# Power.net
KiCad netlist of a schematic drawn in Altium Designer
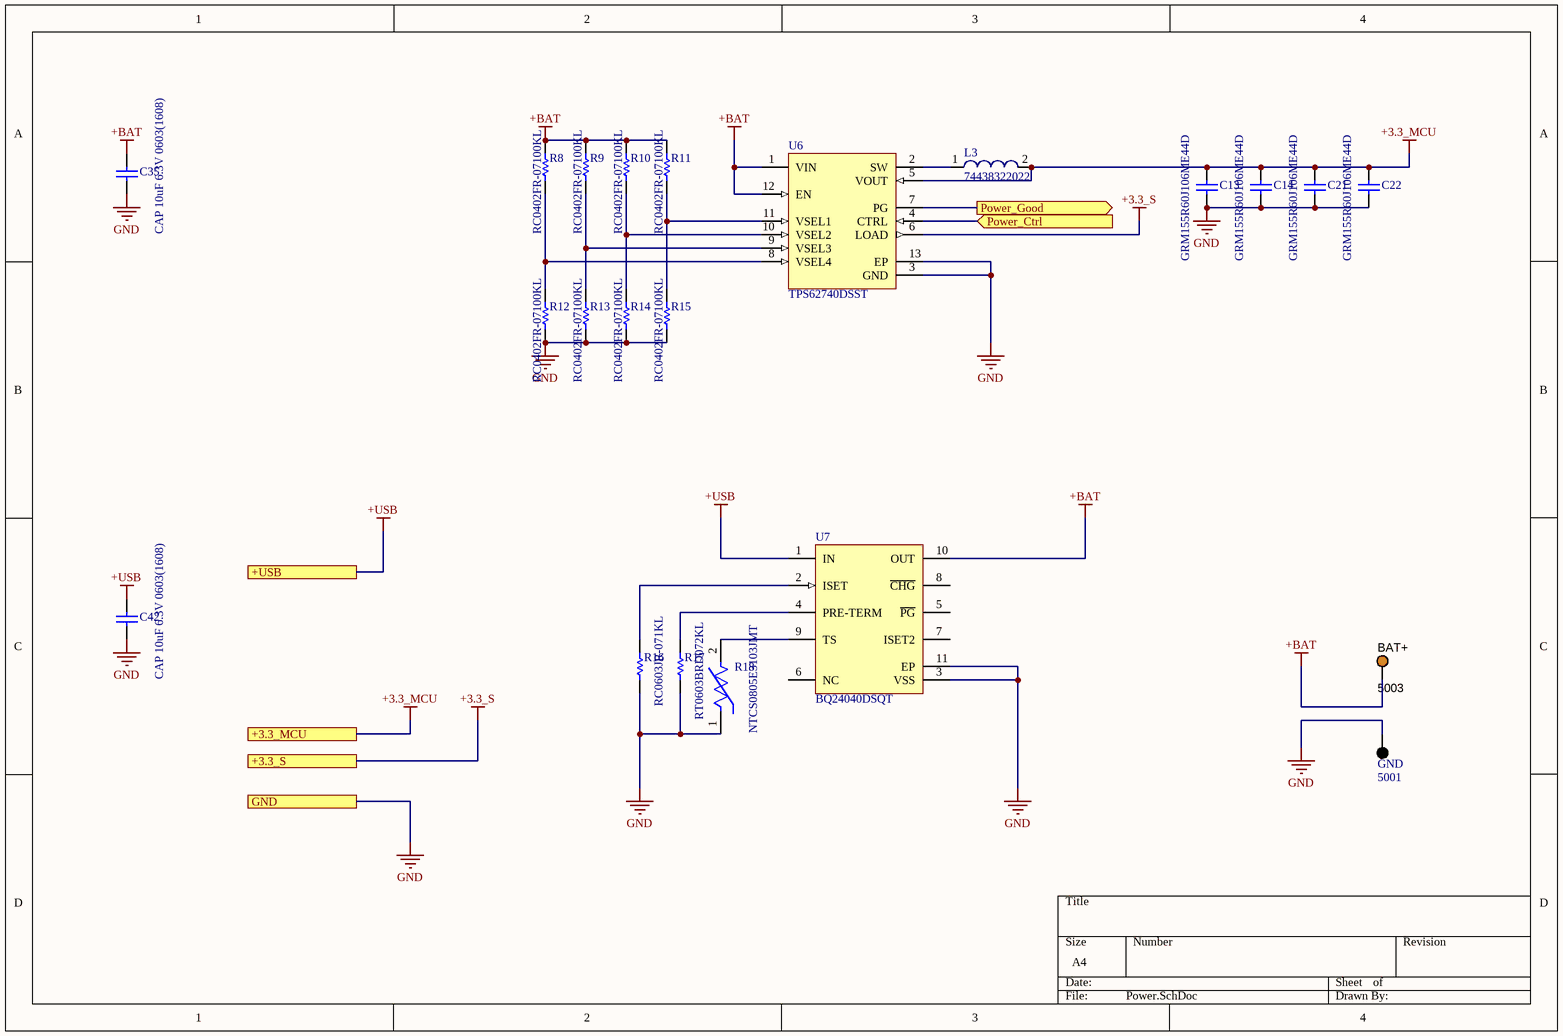
[diagram p0: Power.SchDoc]

(export (version "E")
  (design (tool "Eeschema 10.0.6"))
  (components
    (comp (ref "BAT+")
      (value "5003")
      (footprint "KSTN-5003")
      (description "Test Point, Orange, 1-Pin THD, RoHS")
      (libsource (lib "Altium Content Vault") (part "TESTPOINT_ORANGE"))
    )
    (comp (ref "C13")
      (value "GRM155R60J106ME44D")
      (footprint "MURA-GRM155R60J106ME44D-2_M")
      (fields (field (name "TOLERANCE") "20%") (field (name "MANUFACTURER") "Murata"))
      (libsource (lib "Altium Content Vault") (part "CAP-NP-2"))
    )
    (comp (ref "C14")
      (value "GRM155R60J106ME44D")
      (footprint "MURA-GRM155R60J106ME44D-2_M")
      (fields (field (name "TOLERANCE") "20%") (field (name "MANUFACTURER") "Murata"))
      (libsource (lib "Altium Content Vault") (part "CAP-NP-2"))
    )
    (comp (ref "C21")
      (value "GRM155R60J106ME44D")
      (footprint "MURA-GRM155R60J106ME44D-2_M")
      (fields (field (name "TOLERANCE") "20%") (field (name "MANUFACTURER") "Murata"))
      (libsource (lib "Altium Content Vault") (part "CAP-NP-2"))
    )
    (comp (ref "C22")
      (value "GRM155R60J106ME44D")
      (footprint "MURA-GRM155R60J106ME44D-2_M")
      (fields (field (name "TOLERANCE") "20%") (field (name "MANUFACTURER") "Murata"))
      (libsource (lib "Altium Content Vault") (part "CAP-NP-2"))
    )
    (comp (ref "C35")
      (value "CAP 10uF 6.3V 0603(1608)")
      (footprint "CAPC0603(1608)100_N")
      (description "CAP 10uF 6.3V ±20% 0603 (1608 Metric) Thickness 1mm SMD")
      (fields (field (name "TOLERANCE") "Â±20%"))
      (libsource (lib "Altium Content Vault") (part "CAP"))
    )
    (comp (ref "C42")
      (value "CAP 10uF 6.3V 0603(1608)")
      (footprint "CAPC0603(1608)100_N")
      (description "CAP 10uF 6.3V ±20% 0603 (1608 Metric) Thickness 1mm SMD")
      (fields (field (name "TOLERANCE") "Â±20%"))
      (libsource (lib "Altium Content Vault") (part "CAP"))
    )
    (comp (ref "GND")
      (value "5001")
      (footprint "KSTN-5001")
      (description "Test Point, Black, 1-Pin THD, RoHS, Bulk")
      (fields (field (name "MANUFACTURER") "Keystone"))
      (libsource (lib "Altium Content Vault") (part "KSTN-TP-5001"))
    )
    (comp (ref "L3")
      (value "74438322022")
      (footprint "SMD 2508")
      (description "Power Multilayer Inductor WE-MAPI, L=2.2µH")
      (fields (field (name "MANUFACTURER") "Wuerth Elektronik"))
      (libsource (lib "Altium Content Vault") (part "WE-IND-INDUCTOR-2"))
    )
    (comp (ref "R8")
      (value "RC0402FR-07100KL")
      (footprint "RESC1005X40X25NL05T10")
      (fields (field (name "MANUFACTURER") "Yageo / Phycomp"))
      (libsource (lib "Altium Content Vault") (part "RES"))
    )
    (comp (ref "R9")
      (value "RC0402FR-07100KL")
      (footprint "RESC1005X40X25NL05T10")
      (fields (field (name "MANUFACTURER") "Yageo / Phycomp"))
      (libsource (lib "Altium Content Vault") (part "RES"))
    )
    (comp (ref "R10")
      (value "RC0402FR-07100KL")
      (footprint "RESC1005X40X25NL05T10")
      (fields (field (name "MANUFACTURER") "Yageo / Phycomp"))
      (libsource (lib "Altium Content Vault") (part "RES"))
    )
    (comp (ref "R11")
      (value "RC0402FR-07100KL")
      (footprint "RESC1005X40X25NL05T10")
      (fields (field (name "MANUFACTURER") "Yageo / Phycomp"))
      (libsource (lib "Altium Content Vault") (part "RES"))
    )
    (comp (ref "R12")
      (value "RC0402FR-07100KL")
      (footprint "RESC1005X40X25NL05T10")
      (fields (field (name "MANUFACTURER") "Yageo / Phycomp"))
      (libsource (lib "Altium Content Vault") (part "RES"))
    )
    (comp (ref "R13")
      (value "RC0402FR-07100KL")
      (footprint "RESC1005X40X25NL05T10")
      (fields (field (name "MANUFACTURER") "Yageo / Phycomp"))
      (libsource (lib "Altium Content Vault") (part "RES"))
    )
    (comp (ref "R14")
      (value "RC0402FR-07100KL")
      (footprint "RESC1005X40X25NL05T10")
      (fields (field (name "MANUFACTURER") "Yageo / Phycomp"))
      (libsource (lib "Altium Content Vault") (part "RES"))
    )
    (comp (ref "R15")
      (value "RC0402FR-07100KL")
      (footprint "RESC1005X40X25NL05T10")
      (fields (field (name "MANUFACTURER") "Yageo / Phycomp"))
      (libsource (lib "Altium Content Vault") (part "RES"))
    )
    (comp (ref "R16")
      (value "RC0603JR-071KL")
      (footprint "RESC1608X55X25ML10T15")
      (description "Chip Resistor, 1 KOhm, +/- 5%, 0.063 W, -55 to 155 degC, 0603 (1608 Metric), RoHS, Tape and Reel")
      (fields (field (name "MANUFACTURER") "Yageo"))
      (libsource (lib "Altium Content Vault") (part "RES-2"))
    )
    (comp (ref "R17")
      (value "RT0603BRD072KL")
      (footprint "RESC1608X55X25ML10T15")
      (fields (field (name "MANUFACTURER") "Yageo"))
      (libsource (lib "Altium Content Vault") (part "RES"))
    )
    (comp (ref "R18")
      (value "NTCS0805E3103JMT")
      (footprint "FP-NTCS0805-MFG")
      (description "THERMISTOR NTC 10KOHM 3570K 0805")
      (fields
        (field (name "OCTOPART") "https://octopart.com/ntcs0805e3103jmt-vishay-39723061")
        (field (name "TOLERANCE") "5%")
      )
      (libsource (lib "Altium Content Vault") (part "3b148a6ebabc5fb4d708a66c052d352"))
    )
    (comp (ref "U6")
      (value "TPS62740DSST")
      (footprint "DSS0012A_V")
      (fields (field (name "PARTNUMBER") "TPS62740"))
      (libsource (lib "Altium Content Vault") (part "TI-TPS62740_2-WSON-12"))
    )
    (comp (ref "U7")
      (value "BQ24040DSQT")
      (footprint "DSQ0010A_V")
      (fields (field (name "MANUFACTURER") "Texas Instruments"))
      (libsource (lib "Altium Content Vault") (part "TI-BQ24040DSQ10-1500X900TP"))
    )
  )
  (nets
    (net (code "1") (name "+3.3_MCU") (class "Default")
      (node (ref "C13") (pin "2") (pinfunction "2_2") (pintype "passive"))
      (node (ref "C14") (pin "2") (pinfunction "2_2") (pintype "passive"))
      (node (ref "C21") (pin "2") (pinfunction "2_2") (pintype "passive"))
      (node (ref "C22") (pin "2") (pinfunction "2_2") (pintype "passive"))
      (node (ref "L3") (pin "2") (pinfunction "2_2") (pintype "passive"))
      (node (ref "U6") (pin "5") (pinfunction "VOUT_5") (pintype "input"))
    )
    (net (code "2") (name "+3.3_S") (class "Default")
      (node (ref "U6") (pin "6") (pinfunction "LOAD_6") (pintype "output"))
    )
    (net (code "3") (name "+BAT") (class "Default")
      (node (ref "BAT+") (pin "1") (pinfunction "1_1") (pintype "passive"))
      (node (ref "C35") (pin "2") (pinfunction "2_2") (pintype "passive"))
      (node (ref "R10") (pin "2") (pinfunction "2_2") (pintype "passive"))
      (node (ref "R11") (pin "2") (pinfunction "2_2") (pintype "passive"))
      (node (ref "R8") (pin "2") (pinfunction "2_2") (pintype "passive"))
      (node (ref "R9") (pin "2") (pinfunction "2_2") (pintype "passive"))
      (node (ref "U6") (pin "1") (pinfunction "VIN_1") (pintype "power_in"))
      (node (ref "U6") (pin "12") (pinfunction "EN_12") (pintype "input"))
      (node (ref "U7") (pin "10") (pinfunction "OUT_10") (pintype "power_in"))
    )
    (net (code "4") (name "+USB") (class "Default")
      (node (ref "C42") (pin "2") (pinfunction "2_2") (pintype "passive"))
      (node (ref "U7") (pin "1") (pinfunction "IN_1") (pintype "power_in"))
    )
    (net (code "5") (name "/Power_Ctrl") (class "Default")
      (node (ref "U6") (pin "4") (pinfunction "CTRL_4") (pintype "input"))
    )
    (net (code "6") (name "/Power_Good") (class "Default")
      (node (ref "U6") (pin "7") (pinfunction "PG_7") (pintype "tri_state"))
    )
    (net (code "7") (name "GND") (class "Default")
      (node (ref "C13") (pin "1") (pinfunction "1_1") (pintype "passive"))
      (node (ref "C14") (pin "1") (pinfunction "1_1") (pintype "passive"))
      (node (ref "C21") (pin "1") (pinfunction "1_1") (pintype "passive"))
      (node (ref "C22") (pin "1") (pinfunction "1_1") (pintype "passive"))
      (node (ref "C35") (pin "1") (pinfunction "1_1") (pintype "passive"))
      (node (ref "C42") (pin "1") (pinfunction "1_1") (pintype "passive"))
      (node (ref "GND") (pin "1") (pintype "passive"))
      (node (ref "R12") (pin "1") (pinfunction "1_1") (pintype "passive"))
      (node (ref "R13") (pin "1") (pinfunction "1_1") (pintype "passive"))
      (node (ref "R14") (pin "1") (pinfunction "1_1") (pintype "passive"))
      (node (ref "R15") (pin "1") (pinfunction "1_1") (pintype "passive"))
      (node (ref "R16") (pin "1") (pinfunction "1_1") (pintype "passive"))
      (node (ref "R17") (pin "1") (pinfunction "1_1") (pintype "passive"))
      (node (ref "R18") (pin "1") (pinfunction "1_1") (pintype "passive"))
      (node (ref "U6") (pin "13") (pinfunction "EP_13") (pintype "power_in"))
      (node (ref "U6") (pin "3") (pinfunction "GND_3") (pintype "power_in"))
      (node (ref "U7") (pin "11") (pinfunction "EP_11") (pintype "power_in"))
      (node (ref "U7") (pin "3") (pinfunction "VSS_3") (pintype "power_in"))
    )
    (net (code "8") (name "Net-(U6-SW)") (class "Default")
      (node (ref "L3") (pin "1") (pinfunction "1_1") (pintype "passive"))
      (node (ref "U6") (pin "2") (pinfunction "SW_2") (pintype "power_in"))
    )
    (net (code "9") (name "Net-(U6-VSEL1)") (class "Default")
      (node (ref "R11") (pin "1") (pinfunction "1_1") (pintype "passive"))
      (node (ref "R15") (pin "2") (pinfunction "2_2") (pintype "passive"))
      (node (ref "U6") (pin "11") (pinfunction "VSEL1_11") (pintype "input"))
    )
    (net (code "10") (name "Net-(U6-VSEL2)") (class "Default")
      (node (ref "R10") (pin "1") (pinfunction "1_1") (pintype "passive"))
      (node (ref "R14") (pin "2") (pinfunction "2_2") (pintype "passive"))
      (node (ref "U6") (pin "10") (pinfunction "VSEL2_10") (pintype "input"))
    )
    (net (code "11") (name "Net-(U6-VSEL3)") (class "Default")
      (node (ref "R13") (pin "2") (pinfunction "2_2") (pintype "passive"))
      (node (ref "R9") (pin "1") (pinfunction "1_1") (pintype "passive"))
      (node (ref "U6") (pin "9") (pinfunction "VSEL3_9") (pintype "input"))
    )
    (net (code "12") (name "Net-(U6-VSEL4)") (class "Default")
      (node (ref "R12") (pin "2") (pinfunction "2_2") (pintype "passive"))
      (node (ref "R8") (pin "1") (pinfunction "1_1") (pintype "passive"))
      (node (ref "U6") (pin "8") (pinfunction "VSEL4_8") (pintype "input"))
    )
    (net (code "13") (name "Net-(U7-ISET)") (class "Default")
      (node (ref "R16") (pin "2") (pinfunction "2_2") (pintype "passive"))
      (node (ref "U7") (pin "2") (pinfunction "ISET_2") (pintype "input"))
    )
    (net (code "14") (name "Net-(U7-PRE-TERM)") (class "Default")
      (node (ref "R17") (pin "2") (pinfunction "2_2") (pintype "passive"))
      (node (ref "U7") (pin "4") (pinfunction "PRE-TERM_4") (pintype "passive"))
    )
    (net (code "15") (name "Net-(U7-TS)") (class "Default")
      (node (ref "R18") (pin "2") (pinfunction "2_2") (pintype "passive"))
      (node (ref "U7") (pin "9") (pinfunction "TS_9") (pintype "passive"))
    )
    (net (code "16") (name "unconnected-(U7-ISET2-Pad7)") (class "Default")
      (node (ref "U7") (pin "7") (pinfunction "ISET2_7") (pintype "passive"))
    )
    (net (code "17") (name "unconnected-(U7-NC-Pad6)") (class "Default")
      (node (ref "U7") (pin "6") (pinfunction "NC_6") (pintype "passive"))
    )
    (net (code "18") (name "unconnected-(U7-~{CHG}-Pad8)") (class "Default")
      (node (ref "U7") (pin "8") (pinfunction "~{CHG}_8") (pintype "tri_state"))
    )
    (net (code "19") (name "unconnected-(U7-~{PG}-Pad5)") (class "Default")
      (node (ref "U7") (pin "5") (pinfunction "~{PG}_5") (pintype "tri_state"))
    )
  )
)
